# Amplificador_V03_R00.net
KiCad netlist of a schematic drawn in Altium Designer
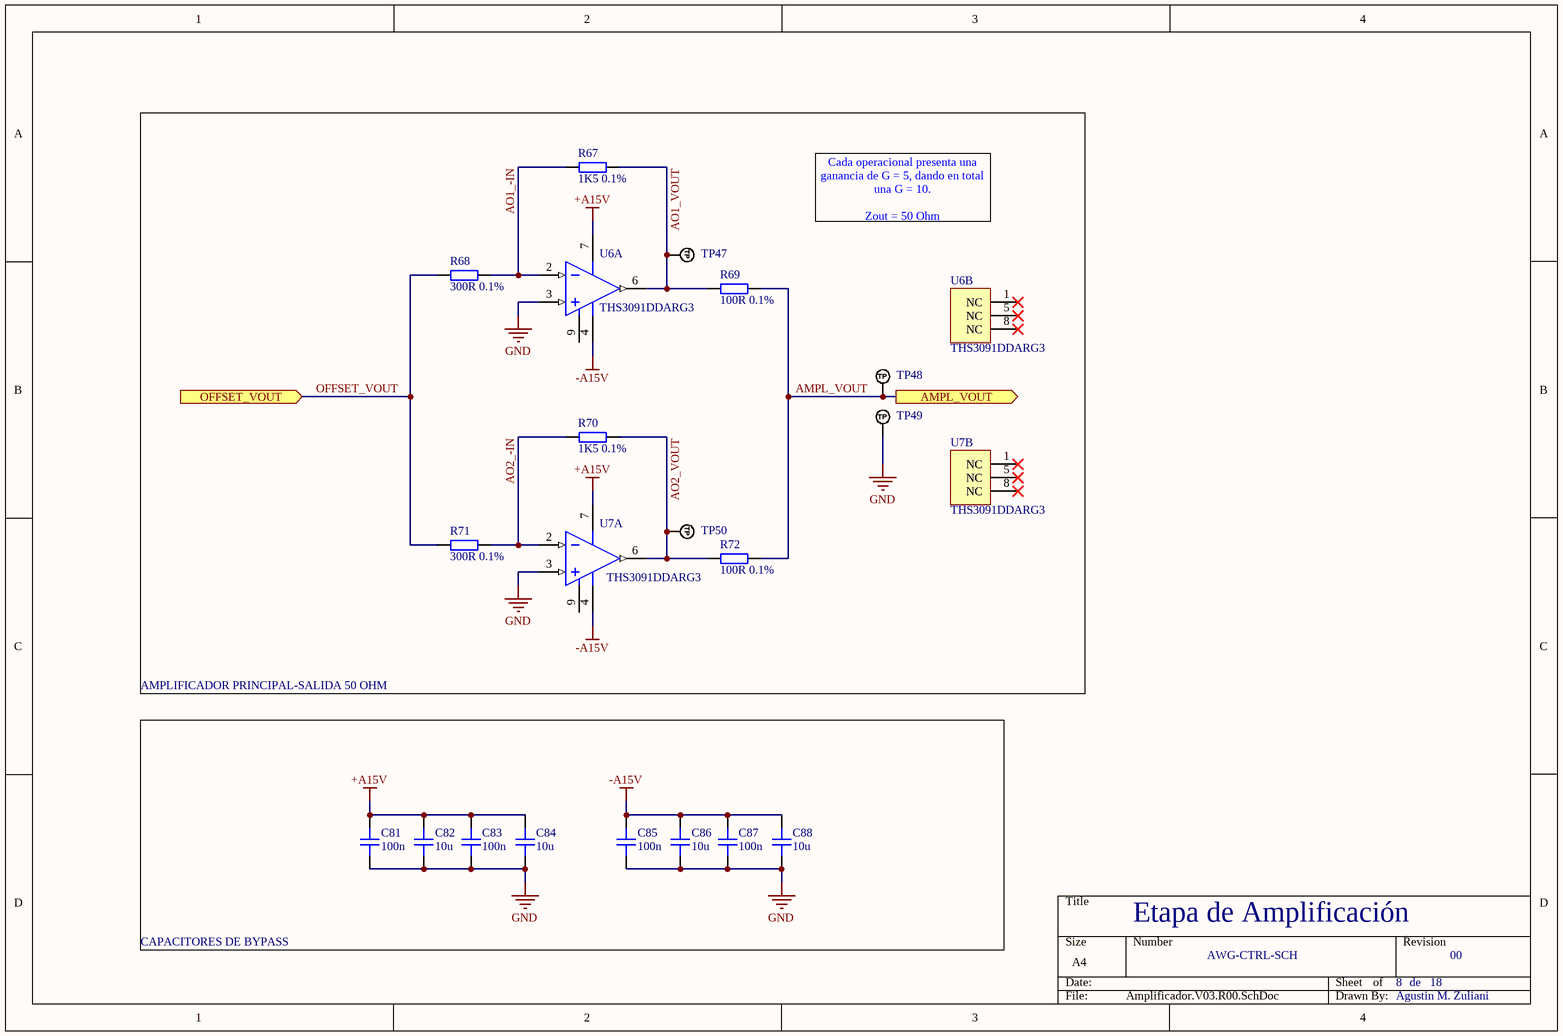
[diagram p0: Amplificador.V03.R00.SchDoc]

(export (version "E")
  (design (tool "Eeschema 10.0.6"))
  (components
    (comp (ref "C81")
      (value "100n")
      (footprint "CAP_0805")
      (description "Capacitor SMD 0805")
      (libsource (lib "Schematic-Lib-PhilsLab") (part "CAP_0805"))
    )
    (comp (ref "C82")
      (value "10u")
      (footprint "CAP_0805")
      (description "Capacitor SMD 0805")
      (libsource (lib "Schematic-Lib-PhilsLab") (part "CAP_0805"))
    )
    (comp (ref "C83")
      (value "100n")
      (footprint "CAP_0805")
      (description "Capacitor SMD 0805")
      (libsource (lib "Schematic-Lib-PhilsLab") (part "CAP_0805"))
    )
    (comp (ref "C84")
      (value "10u")
      (footprint "CAP_0805")
      (description "Capacitor SMD 0805")
      (libsource (lib "Schematic-Lib-PhilsLab") (part "CAP_0805"))
    )
    (comp (ref "C85")
      (value "100n")
      (footprint "CAP_0805")
      (description "Capacitor SMD 0805")
      (libsource (lib "Schematic-Lib-PhilsLab") (part "CAP_0805"))
    )
    (comp (ref "C86")
      (value "10u")
      (footprint "CAP_0805")
      (description "Capacitor SMD 0805")
      (libsource (lib "Schematic-Lib-PhilsLab") (part "CAP_0805"))
    )
    (comp (ref "C87")
      (value "100n")
      (footprint "CAP_0805")
      (description "Capacitor SMD 0805")
      (libsource (lib "Schematic-Lib-PhilsLab") (part "CAP_0805"))
    )
    (comp (ref "C88")
      (value "10u")
      (footprint "CAP_0805")
      (description "Capacitor SMD 0805")
      (libsource (lib "Schematic-Lib-PhilsLab") (part "CAP_0805"))
    )
    (comp (ref "R67")
      (value "1K5 0.1%")
      (footprint "RES_0805")
      (description "Resistor SMD 0805")
      (libsource (lib "Schematic-Lib-PhilsLab") (part "RES_0805"))
    )
    (comp (ref "R68")
      (value "300R 0.1%")
      (footprint "RES_0805")
      (description "Resistor SMD 0805")
      (libsource (lib "Schematic-Lib-PhilsLab") (part "RES_0805"))
    )
    (comp (ref "R69")
      (value "100R 0.1%")
      (footprint "RES_0805")
      (description "Resistor SMD 0805")
      (libsource (lib "Schematic-Lib-PhilsLab") (part "RES_0805"))
    )
    (comp (ref "R70")
      (value "1K5 0.1%")
      (footprint "RES_0805")
      (description "Resistor SMD 0805")
      (libsource (lib "Schematic-Lib-PhilsLab") (part "RES_0805"))
    )
    (comp (ref "R71")
      (value "300R 0.1%")
      (footprint "RES_0805")
      (description "Resistor SMD 0805")
      (libsource (lib "Schematic-Lib-PhilsLab") (part "RES_0805"))
    )
    (comp (ref "R72")
      (value "100R 0.1%")
      (footprint "RES_0805")
      (description "Resistor SMD 0805")
      (libsource (lib "Schematic-Lib-PhilsLab") (part "RES_0805"))
    )
    (comp (ref "TP47")
      (value "TP_NOBOM")
      (footprint "PAD_RND_1MM")
      (description "Test Point Round 1mm (NO BOM)")
      (libsource (lib "Schematic-Lib-PhilsLab") (part "TEST_POINT_RND_1MM"))
    )
    (comp (ref "TP48")
      (value "TP_NOBOM")
      (footprint "PAD_RND_1MM")
      (description "Test Point Round 1mm (NO BOM)")
      (libsource (lib "Schematic-Lib-PhilsLab") (part "TEST_POINT_RND_1MM"))
    )
    (comp (ref "TP49")
      (value "TP_NOBOM")
      (footprint "PAD_RND_1MM")
      (description "Test Point Round 1mm (NO BOM)")
      (libsource (lib "Schematic-Lib-PhilsLab") (part "TEST_POINT_RND_1MM"))
    )
    (comp (ref "TP50")
      (value "TP_NOBOM")
      (footprint "PAD_RND_1MM")
      (description "Test Point Round 1mm (NO BOM)")
      (libsource (lib "Schematic-Lib-PhilsLab") (part "TEST_POINT_RND_1MM"))
    )
    (comp (ref "U6")
      (value "THS3091DDARG3")
      (footprint "TI-DDA8-1775X1775TP_M")
      (fields (field (name "MANUFACTURER") "Texas Instruments"))
      (libsource (lib "Altium Content Vault") (part "TI-AMP-S3-2-DDA8"))
    )
    (comp (ref "U7")
      (value "THS3091DDARG3")
      (footprint "TI-DDA8-1775X1775TP_M")
      (fields (field (name "MANUFACTURER") "Texas Instruments"))
      (libsource (lib "Altium Content Vault") (part "TI-AMP-S3-2-DDA8"))
    )
  )
  (nets
    (net (code "1") (name "+A15V") (class "Default")
      (node (ref "C81") (pin "1") (pinfunction "1_1") (pintype "passive"))
      (node (ref "C82") (pin "1") (pinfunction "1_1") (pintype "passive"))
      (node (ref "C83") (pin "1") (pinfunction "1_1") (pintype "passive"))
      (node (ref "C84") (pin "1") (pinfunction "1_1") (pintype "passive"))
      (node (ref "U6") (pin "7") (pinfunction "VS+_7") (pintype "power_in"))
      (node (ref "U7") (pin "7") (pinfunction "VS+_7") (pintype "power_in"))
    )
    (net (code "2") (name "-A15V") (class "Default")
      (node (ref "C85") (pin "1") (pinfunction "1_1") (pintype "passive"))
      (node (ref "C86") (pin "1") (pinfunction "1_1") (pintype "passive"))
      (node (ref "C87") (pin "1") (pinfunction "1_1") (pintype "passive"))
      (node (ref "C88") (pin "1") (pinfunction "1_1") (pintype "passive"))
      (node (ref "U6") (pin "4") (pinfunction "VS-_4") (pintype "power_in"))
      (node (ref "U7") (pin "4") (pinfunction "VS-_4") (pintype "power_in"))
    )
    (net (code "3") (name "/AMPL_VOUT") (class "Default")
      (node (ref "R69") (pin "2") (pinfunction "2_2") (pintype "passive"))
      (node (ref "R72") (pin "2") (pinfunction "2_2") (pintype "passive"))
      (node (ref "TP48") (pin "1") (pinfunction "TP_1") (pintype "passive"))
    )
    (net (code "4") (name "/AO1_-IN") (class "Default")
      (node (ref "R67") (pin "1") (pinfunction "1_1") (pintype "passive"))
      (node (ref "R68") (pin "2") (pinfunction "2_2") (pintype "passive"))
      (node (ref "U6") (pin "2") (pinfunction "VIN-_2") (pintype "input"))
    )
    (net (code "5") (name "/AO1_VOUT") (class "Default")
      (node (ref "R67") (pin "2") (pinfunction "2_2") (pintype "passive"))
      (node (ref "R69") (pin "1") (pinfunction "1_1") (pintype "passive"))
      (node (ref "TP47") (pin "1") (pinfunction "TP_1") (pintype "passive"))
      (node (ref "U6") (pin "6") (pinfunction "VOUT_6") (pintype "output"))
    )
    (net (code "6") (name "/AO2_-IN") (class "Default")
      (node (ref "R70") (pin "1") (pinfunction "1_1") (pintype "passive"))
      (node (ref "R71") (pin "2") (pinfunction "2_2") (pintype "passive"))
      (node (ref "U7") (pin "2") (pinfunction "VIN-_2") (pintype "input"))
    )
    (net (code "7") (name "/AO2_VOUT") (class "Default")
      (node (ref "R70") (pin "2") (pinfunction "2_2") (pintype "passive"))
      (node (ref "R72") (pin "1") (pinfunction "1_1") (pintype "passive"))
      (node (ref "TP50") (pin "1") (pinfunction "TP_1") (pintype "passive"))
      (node (ref "U7") (pin "6") (pinfunction "VOUT_6") (pintype "output"))
    )
    (net (code "8") (name "/OFFSET_VOUT") (class "Default")
      (node (ref "R68") (pin "1") (pinfunction "1_1") (pintype "passive"))
      (node (ref "R71") (pin "1") (pinfunction "1_1") (pintype "passive"))
    )
    (net (code "9") (name "GND") (class "Default")
      (node (ref "C81") (pin "2") (pinfunction "2_2") (pintype "passive"))
      (node (ref "C82") (pin "2") (pinfunction "2_2") (pintype "passive"))
      (node (ref "C83") (pin "2") (pinfunction "2_2") (pintype "passive"))
      (node (ref "C84") (pin "2") (pinfunction "2_2") (pintype "passive"))
      (node (ref "C85") (pin "2") (pinfunction "2_2") (pintype "passive"))
      (node (ref "C86") (pin "2") (pinfunction "2_2") (pintype "passive"))
      (node (ref "C87") (pin "2") (pinfunction "2_2") (pintype "passive"))
      (node (ref "C88") (pin "2") (pinfunction "2_2") (pintype "passive"))
      (node (ref "TP49") (pin "1") (pinfunction "TP_1") (pintype "passive"))
      (node (ref "U6") (pin "3") (pinfunction "VIN+_3") (pintype "input"))
      (node (ref "U7") (pin "3") (pinfunction "VIN+_3") (pintype "input"))
    )
    (net (code "10") (name "unconnected-(U6A-EP-Pad9)") (class "Default")
      (node (ref "U6") (pin "9") (pinfunction "EP_9") (pintype "passive"))
    )
    (net (code "11") (name "unconnected-(U6B-NC-Pad1)") (class "Default")
      (node (ref "U6") (pin "1") (pinfunction "NC_1") (pintype "passive+no_connect"))
    )
    (net (code "12") (name "unconnected-(U6B-NC-Pad5)") (class "Default")
      (node (ref "U6") (pin "5") (pinfunction "NC_5") (pintype "passive+no_connect"))
    )
    (net (code "13") (name "unconnected-(U6B-NC-Pad8)") (class "Default")
      (node (ref "U6") (pin "8") (pinfunction "NC_8") (pintype "passive+no_connect"))
    )
    (net (code "14") (name "unconnected-(U7A-EP-Pad9)") (class "Default")
      (node (ref "U7") (pin "9") (pinfunction "EP_9") (pintype "passive"))
    )
    (net (code "15") (name "unconnected-(U7B-NC-Pad1)") (class "Default")
      (node (ref "U7") (pin "1") (pinfunction "NC_1") (pintype "passive+no_connect"))
    )
    (net (code "16") (name "unconnected-(U7B-NC-Pad5)") (class "Default")
      (node (ref "U7") (pin "5") (pinfunction "NC_5") (pintype "passive+no_connect"))
    )
    (net (code "17") (name "unconnected-(U7B-NC-Pad8)") (class "Default")
      (node (ref "U7") (pin "8") (pinfunction "NC_8") (pintype "passive+no_connect"))
    )
  )
)
